# VoltageRegulators.net
KiCad netlist of a schematic drawn in Altium Designer
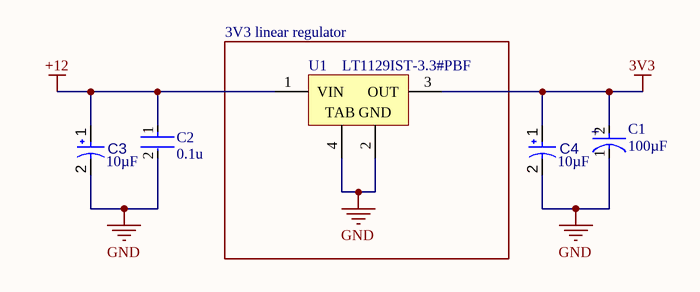
[diagram p0: VoltageRegulators.SchDoc]

(export (version "E")
  (design (tool "Eeschema 10.0.6"))
  (components
    (comp (ref "C1")
      (value "100µF")
      (footprint "FP-T491X107K025AT-MFG")
      (description "CAP TANT 100UF 10% 25V 2917")
      (fields (field (name "TOLERANCE") "10%") (field (name "VOLTAGE") "25V"))
      (libsource (lib "Altium Content Vault") (part "cf48714ba7e38822c1575c7ec0b6d1f"))
    )
    (comp (ref "C2")
      (value "0.1u")
      (footprint "FP-C0603C-CF-MFG")
      (description "CAP CER 0.1UF 50V X7R 0603")
      (fields (field (name "TOLERANCE") "0.1") (field (name "MANUFACTURER") "KEMET"))
      (libsource (lib "Altium Content Vault") (part "b4654b650e69147ec39a6b967a45e02"))
    )
    (comp (ref "C3")
      (value "10µF")
      (footprint "CAPMP3217X18-T_V")
      (description "Standard Tantalum, 10 uF, +/- 10%, 16 V, -55 to 125 degC, 1206 (3216 Metric), RoHS, Tape and Reel")
      (fields (field (name "TOLERANCE") "10%") (field (name "MANUFACTURER") "AVX"))
      (libsource (lib "Bronco Racing") (part "CAP-P-2"))
    )
    (comp (ref "C4")
      (value "10µF")
      (footprint "CAPMP3217X18-T_V")
      (description "Standard Tantalum, 10 uF, +/- 10%, 16 V, -55 to 125 degC, 1206 (3216 Metric), RoHS, Tape and Reel")
      (fields (field (name "TOLERANCE") "10%") (field (name "MANUFACTURER") "AVX"))
      (libsource (lib "Bronco Racing") (part "CAP-P-2"))
    )
    (comp (ref "U1")
      (value "LT1129IST-3.3#PBF")
      (footprint "LT-ST-3-SOT-223_L")
      (fields (field (name "MANUFACTURER") "Linear Technology"))
      (libsource (lib "Altium Content Vault") (part "LT-LT112X-ST-3"))
    )
  )
  (nets
    (net (code "1") (name "+12") (class "Default")
      (node (ref "C2") (pin "1") (pinfunction "1_1") (pintype "passive"))
      (node (ref "C3") (pin "1") (pinfunction "1_1") (pintype "passive"))
      (node (ref "U1") (pin "1") (pinfunction "VIN_1") (pintype "power_in"))
    )
    (net (code "2") (name "3V3") (class "Default")
      (node (ref "C1") (pin "2") (pinfunction "A_2") (pintype "passive"))
      (node (ref "C4") (pin "1") (pinfunction "1_1") (pintype "passive"))
      (node (ref "U1") (pin "3") (pinfunction "OUT_3") (pintype "power_in"))
    )
    (net (code "3") (name "GND") (class "Default")
      (node (ref "C1") (pin "1") (pinfunction "C_1") (pintype "passive"))
      (node (ref "C2") (pin "2") (pinfunction "2_2") (pintype "passive"))
      (node (ref "C3") (pin "2") (pinfunction "2_2") (pintype "passive"))
      (node (ref "C4") (pin "2") (pinfunction "2_2") (pintype "passive"))
      (node (ref "U1") (pin "2") (pinfunction "GND_2") (pintype "power_in"))
      (node (ref "U1") (pin "4") (pinfunction "TAB_4") (pintype "power_in"))
    )
  )
)
